# uCCtrl.net
KiCad netlist of a schematic drawn in Altium Designer
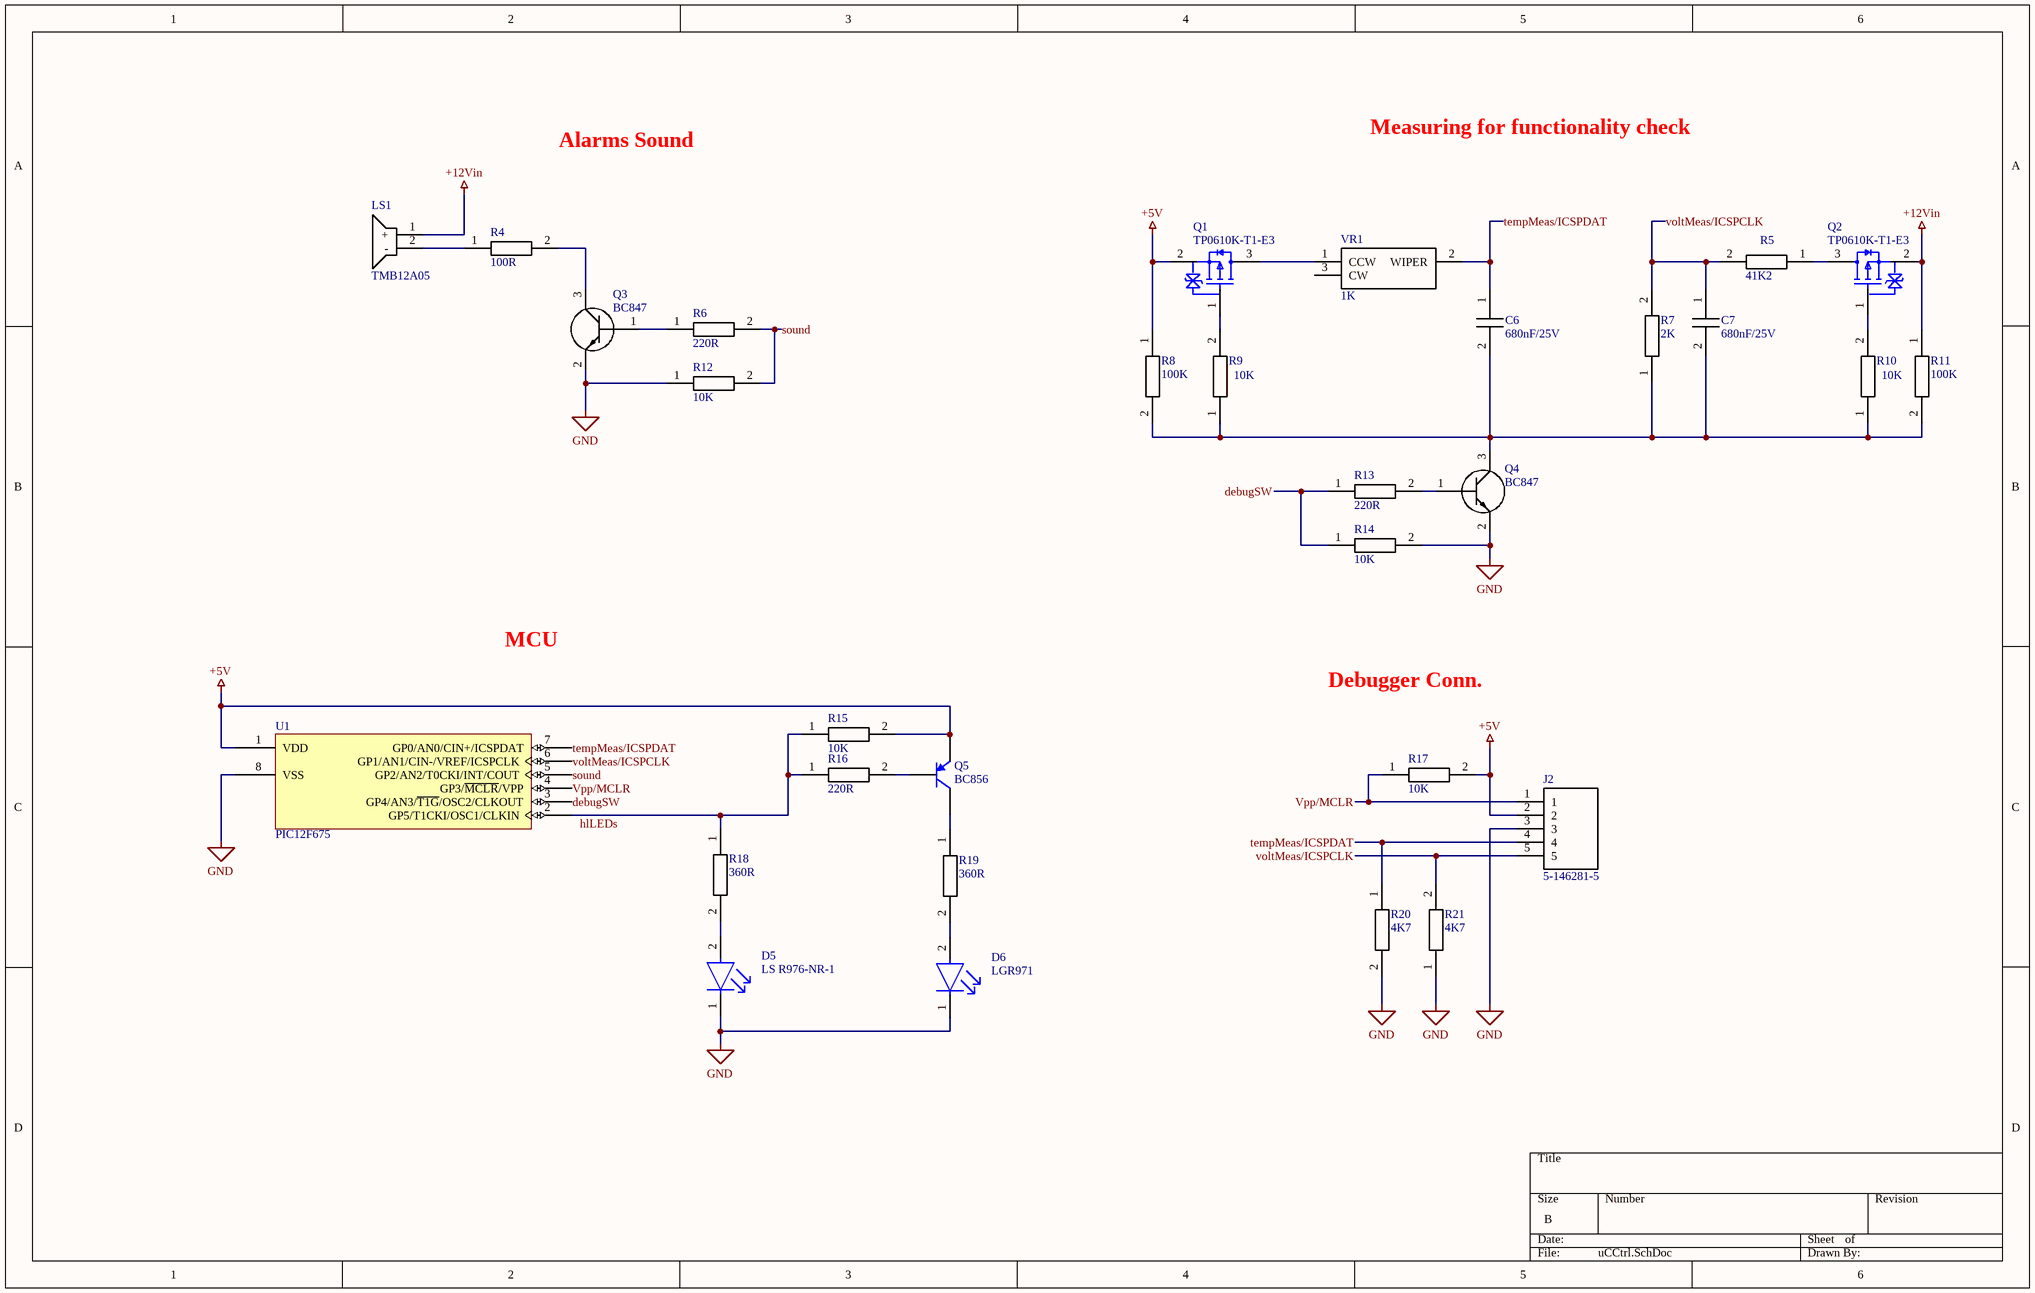
[diagram p0: uCCtrl.SchDoc]

(export (version "E")
  (design (tool "Eeschema 10.0.6"))
  (components
    (comp (ref "C6")
      (value "680nF/25V")
      (footprint "SamacSys:CAPC2012X95N")
      (description "Capacitor")
      (fields (field (name "MANUFACTURER_PART_NUMBER") "GRM219B31E684KA88D"))
      (libsource (lib "*") (part "GRM219B31E684KA88D"))
    )
    (comp (ref "C7")
      (value "680nF/25V")
      (footprint "SamacSys:CAPC2012X95N")
      (description "Capacitor")
      (fields (field (name "MANUFACTURER_PART_NUMBER") "GRM219B31E684KA88D"))
      (libsource (lib "*") (part "GRM219B31E684KA88D"))
    )
    (comp (ref "D5")
      (value "LS R976-NR-1")
      (footprint "FP-LS_R976-MFG")
      (description "LED RED DIFFUSED 0805 SMD")
      (libsource (lib "Altium Content Vault") (part "8706943c75ba83719d021d2fdc84c58"))
    )
    (comp (ref "D6")
      (value "LGR971")
      (footprint "FP-LG_R971-MFG")
      (description "LED GREEN DIFFUSED 0805 SMD")
      (libsource (lib "Altium Content Vault") (part "8706943c75ba83719d021d2fdc84c58"))
    )
    (comp (ref "J2")
      (value "5-146281-5")
      (footprint "SamacSys:HDRV5W67P0X254_1X5_1229X234X821P")
      (description "Connector")
      (fields (field (name "MOUSER PART NUMBER") "571-5-146281-5"))
      (libsource (lib "*") (part "5-146281-5"))
    )
    (comp (ref "LS1")
      (value "TMB12A05")
      (footprint "SamacSys:TMB12A05")
      (description "Loudspeaker or Buzzer")
      (libsource (lib "*") (part "TMB12A05"))
    )
    (comp (ref "Q1")
      (value "TP0610K-T1-E3")
      (footprint "FP-S-03946-MFG")
      (description "MOSFET P-CH 60V 185MA SOT23-3")
      (fields
        (field (name "MANUFACTURER") "Vishay")
        (field (name "OCTOPART") "https://octopart.com/tp0610k-t1-e3-vishay-40944172")
      )
      (libsource (lib "Altium Content Vault") (part "bc9d61678d3f6143cc1ffb3a369bd6c"))
    )
    (comp (ref "Q2")
      (value "TP0610K-T1-E3")
      (footprint "FP-S-03946-MFG")
      (description "MOSFET P-CH 60V 185MA SOT23-3")
      (fields
        (field (name "MANUFACTURER") "Vishay")
        (field (name "OCTOPART") "https://octopart.com/tp0610k-t1-e3-vishay-40944172")
      )
      (libsource (lib "Altium Content Vault") (part "bc9d61678d3f6143cc1ffb3a369bd6c"))
    )
    (comp (ref "Q3")
      (value "BC847")
      (footprint "SamacSys:BC847215")
      (description "Transistor BJT NPN")
      (fields
        (field (name "MANUFACTURER_PART_NUMBER") "BC847,215")
        (field (name "MOUSER PART NUMBER") "771-BC847215")
      )
      (libsource (lib "*") (part "BC847,215"))
    )
    (comp (ref "Q4")
      (value "BC847")
      (footprint "SamacSys:BC847215")
      (description "Transistor BJT NPN")
      (fields
        (field (name "MANUFACTURER_PART_NUMBER") "BC847,215")
        (field (name "MOUSER PART NUMBER") "771-BC847215")
      )
      (libsource (lib "*") (part "BC847,215"))
    )
    (comp (ref "Q5")
      (value "BC856")
      (footprint "NXP-SOT23-3_V")
      (description "PNP General Purpose Transistor, 65 V, -65 to 150 degC, 3-Pin SOT23, RoHS")
      (fields (field (name "MANUFACTURER") "NXP"))
      (libsource (lib "Altium Content Vault") (part "BJT-PNP-BEC-3"))
    )
    (comp (ref "R4")
      (value "100R")
      (footprint "SamacSys:RESC2012X60N")
      (description "Resistor")
      (fields
        (field (name "MANUFACTURER_PART_NUMBER") "CRCW0805100RFKEAHP")
        (field (name "MOUSER PART NUMBER") "71-CRCW0805100RFKEAH")
      )
      (libsource (lib "*") (part "CRCW0805100RFKEAHP"))
    )
    (comp (ref "R5")
      (value "41K2")
      (footprint "SamacSys:RESC2012X65N")
      (description "Resistor")
      (fields (field (name "MANUFACTURER_PART_NUMBER") "CPF0805B41K2E1"))
      (libsource (lib "*") (part "CPF0805B41K2E1"))
    )
    (comp (ref "R6")
      (value "220R")
      (footprint "SamacSys:RESC2012X65N")
      (description "Resistor")
      (fields (field (name "MANUFACTURER_PART_NUMBER") "CPF0805B220RE"))
      (libsource (lib "*") (part "CPF0805B220RE"))
    )
    (comp (ref "R7")
      (value "2K")
      (footprint "SamacSys:RESC2012X65N")
      (description "Resistor")
      (fields
        (field (name "MANUFACTURER_PART_NUMBER") "CPF0805B360RE1")
        (field (name "MOUSER PART NUMBER") "279-CPF0805B360RE1")
      )
      (libsource (lib "*") (part "CPF0805B360RE1"))
    )
    (comp (ref "R8")
      (value "100K")
      (footprint "SamacSys:RESC2012X65N")
      (description "Resistor")
      (fields
        (field (name "MANUFACTURER_PART_NUMBER") "CPF0805B360RE1")
        (field (name "MOUSER PART NUMBER") "279-CPF0805B360RE1")
      )
      (libsource (lib "*") (part "CPF0805B360RE1"))
    )
    (comp (ref "R9")
      (value "10K")
      (footprint "SamacSys:RESC2012X65N")
      (description "Resistor")
      (fields
        (field (name "MANUFACTURER_PART_NUMBER") "CPF0805B360RE1")
        (field (name "MOUSER PART NUMBER") "279-CPF0805B360RE1")
      )
      (libsource (lib "*") (part "CPF0805B360RE1"))
    )
    (comp (ref "R10")
      (value "10K")
      (footprint "SamacSys:RESC2012X65N")
      (description "Resistor")
      (fields
        (field (name "MANUFACTURER_PART_NUMBER") "CPF0805B360RE1")
        (field (name "MOUSER PART NUMBER") "279-CPF0805B360RE1")
      )
      (libsource (lib "*") (part "CPF0805B360RE1"))
    )
    (comp (ref "R11")
      (value "100K")
      (footprint "SamacSys:RESC2012X65N")
      (description "Resistor")
      (fields
        (field (name "MANUFACTURER_PART_NUMBER") "CPF0805B360RE1")
        (field (name "MOUSER PART NUMBER") "279-CPF0805B360RE1")
      )
      (libsource (lib "*") (part "CPF0805B360RE1"))
    )
    (comp (ref "R12")
      (value "10K")
      (footprint "SamacSys:RESC2012X65N")
      (description "Resistor")
      (fields (field (name "MANUFACTURER_PART_NUMBER") "CPF0805B220RE"))
      (libsource (lib "*") (part "CPF0805B220RE"))
    )
    (comp (ref "R13")
      (value "220R")
      (footprint "SamacSys:RESC2012X65N")
      (description "Resistor")
      (fields (field (name "MANUFACTURER_PART_NUMBER") "CPF0805B220RE"))
      (libsource (lib "*") (part "CPF0805B220RE"))
    )
    (comp (ref "R14")
      (value "10K")
      (footprint "SamacSys:RESC2012X65N")
      (description "Resistor")
      (fields (field (name "MANUFACTURER_PART_NUMBER") "CPF0805B220RE"))
      (libsource (lib "*") (part "CPF0805B220RE"))
    )
    (comp (ref "R15")
      (value "10K")
      (footprint "SamacSys:RESC2012X65N")
      (description "Resistor")
      (fields (field (name "MANUFACTURER_PART_NUMBER") "CPF0805B220RE"))
      (libsource (lib "*") (part "CPF0805B220RE"))
    )
    (comp (ref "R16")
      (value "220R")
      (footprint "SamacSys:RESC2012X65N")
      (description "Resistor")
      (fields (field (name "MANUFACTURER_PART_NUMBER") "CPF0805B220RE"))
      (libsource (lib "*") (part "CPF0805B220RE"))
    )
    (comp (ref "R17")
      (value "10K")
      (footprint "SamacSys:RESC2012X65N")
      (description "Resistor")
      (fields
        (field (name "MANUFACTURER_PART_NUMBER") "CPF0805B360RE1")
        (field (name "MOUSER PART NUMBER") "279-CPF0805B360RE1")
      )
      (libsource (lib "*") (part "CPF0805B360RE1"))
    )
    (comp (ref "R18")
      (value "360R")
      (footprint "SamacSys:RESC2012X65N")
      (description "Resistor")
      (fields
        (field (name "MANUFACTURER_PART_NUMBER") "CPF0805B360RE1")
        (field (name "MOUSER PART NUMBER") "279-CPF0805B360RE1")
      )
      (libsource (lib "*") (part "CPF0805B360RE1"))
    )
    (comp (ref "R19")
      (value "360R")
      (footprint "SamacSys:RESC2012X65N")
      (description "Resistor")
      (fields
        (field (name "MANUFACTURER_PART_NUMBER") "CPF0805B360RE1")
        (field (name "MOUSER PART NUMBER") "279-CPF0805B360RE1")
      )
      (libsource (lib "*") (part "CPF0805B360RE1"))
    )
    (comp (ref "R20")
      (value "4K7")
      (footprint "SamacSys:RESC2012X65N")
      (description "Resistor")
      (fields
        (field (name "MANUFACTURER_PART_NUMBER") "CPF0805B360RE1")
        (field (name "MOUSER PART NUMBER") "279-CPF0805B360RE1")
      )
      (libsource (lib "*") (part "CPF0805B360RE1"))
    )
    (comp (ref "R21")
      (value "4K7")
      (footprint "SamacSys:RESC2012X65N")
      (description "Resistor")
      (fields
        (field (name "MANUFACTURER_PART_NUMBER") "CPF0805B360RE1")
        (field (name "MOUSER PART NUMBER") "279-CPF0805B360RE1")
      )
      (libsource (lib "*") (part "CPF0805B360RE1"))
    )
    (comp (ref "U1")
      (value "PIC12F675")
      (footprint "PDIP300-P8")
      (description "FLASH-Based 8-Bit CMOS Microcontroller, 10-Bit A/D, 8-Pin PDIP, Industrial Temperature")
      (libsource (lib "Altium Content Vault") (part "MC-8B-12F675-IL8"))
    )
    (comp (ref "VR1")
      (value "1K")
      (footprint "SamacSys:23SR1KLFTR")
      (description "Variable Resistor")
      (fields (field (name "MANUFACTURER_PART_NUMBER") "23SR1KLFTR"))
      (libsource (lib "*") (part "23SR1KLFTR"))
    )
  )
  (nets
    (net (code "1") (name "+5V") (class "Default")
      (node (ref "J2") (pin "2") (pinfunction "2_2") (pintype "passive"))
      (node (ref "Q1") (pin "2") (pinfunction "S_2") (pintype "passive"))
      (node (ref "Q5") (pin "2") (pinfunction "E_2") (pintype "passive"))
      (node (ref "R15") (pin "2") (pinfunction "2_2") (pintype "passive"))
      (node (ref "R17") (pin "2") (pinfunction "2_2") (pintype "passive"))
      (node (ref "R8") (pin "1") (pinfunction "1_1") (pintype "passive"))
      (node (ref "U1") (pin "1") (pinfunction "VDD_1") (pintype "power_in"))
    )
    (net (code "2") (name "+12Vin") (class "Default")
      (node (ref "LS1") (pin "1") (pinfunction "+_1") (pintype "passive"))
      (node (ref "Q2") (pin "2") (pinfunction "S_2") (pintype "passive"))
      (node (ref "R11") (pin "1") (pinfunction "1_1") (pintype "passive"))
    )
    (net (code "3") (name "/Vpp{slash}MCLR") (class "Default")
      (node (ref "J2") (pin "1") (pinfunction "1_1") (pintype "passive"))
      (node (ref "R17") (pin "1") (pinfunction "1_1") (pintype "passive"))
      (node (ref "U1") (pin "4") (pinfunction "GP3/~{MCLR}/VPP_4") (pintype "bidirectional"))
    )
    (net (code "4") (name "/debugSW") (class "Default")
      (node (ref "R13") (pin "1") (pinfunction "1_1") (pintype "passive"))
      (node (ref "R14") (pin "1") (pinfunction "1_1") (pintype "passive"))
      (node (ref "U1") (pin "3") (pinfunction "GP4/AN3/~{T1G}/OSC2/CLKOUT_3") (pintype "bidirectional"))
    )
    (net (code "5") (name "/hlLEDs") (class "Default")
      (node (ref "R15") (pin "1") (pinfunction "1_1") (pintype "passive"))
      (node (ref "R16") (pin "1") (pinfunction "1_1") (pintype "passive"))
      (node (ref "R18") (pin "1") (pinfunction "1_1") (pintype "passive"))
      (node (ref "U1") (pin "2") (pinfunction "GP5/T1CKI/OSC1/CLKIN_2") (pintype "bidirectional"))
    )
    (net (code "6") (name "/sound") (class "Default")
      (node (ref "R12") (pin "2") (pinfunction "2_2") (pintype "passive"))
      (node (ref "R6") (pin "2") (pinfunction "2_2") (pintype "passive"))
      (node (ref "U1") (pin "5") (pinfunction "GP2/AN2/T0CKI/INT/COUT_5") (pintype "bidirectional"))
    )
    (net (code "7") (name "/tempMeas{slash}ICSPDAT") (class "Default")
      (node (ref "C6") (pin "1") (pinfunction "1_1") (pintype "passive"))
      (node (ref "J2") (pin "4") (pinfunction "4_4") (pintype "passive"))
      (node (ref "R20") (pin "1") (pinfunction "1_1") (pintype "passive"))
      (node (ref "U1") (pin "7") (pinfunction "GP0/AN0/CIN+/ICSPDAT_7") (pintype "bidirectional"))
      (node (ref "VR1") (pin "2") (pinfunction "WIPER_2") (pintype "passive"))
    )
    (net (code "8") (name "/voltMeas{slash}ICSPCLK") (class "Default")
      (node (ref "C7") (pin "1") (pinfunction "1_1") (pintype "passive"))
      (node (ref "J2") (pin "5") (pinfunction "5_5") (pintype "passive"))
      (node (ref "R21") (pin "2") (pinfunction "2_2") (pintype "passive"))
      (node (ref "R5") (pin "2") (pinfunction "2_2") (pintype "passive"))
      (node (ref "R7") (pin "2") (pinfunction "2_2") (pintype "passive"))
      (node (ref "U1") (pin "6") (pinfunction "GP1/AN1/CIN-/VREF/ICSPCLK_6") (pintype "bidirectional"))
    )
    (net (code "9") (name "GND") (class "Default")
      (node (ref "D5") (pin "1") (pinfunction "C_1") (pintype "passive"))
      (node (ref "D6") (pin "1") (pinfunction "C_1") (pintype "passive"))
      (node (ref "J2") (pin "3") (pinfunction "3_3") (pintype "passive"))
      (node (ref "Q3") (pin "2") (pinfunction "E_2") (pintype "passive"))
      (node (ref "Q4") (pin "2") (pinfunction "E_2") (pintype "passive"))
      (node (ref "R12") (pin "1") (pinfunction "1_1") (pintype "passive"))
      (node (ref "R14") (pin "2") (pinfunction "2_2") (pintype "passive"))
      (node (ref "R20") (pin "2") (pinfunction "2_2") (pintype "passive"))
      (node (ref "R21") (pin "1") (pinfunction "1_1") (pintype "passive"))
      (node (ref "U1") (pin "8") (pinfunction "VSS_8") (pintype "power_in"))
    )
    (net (code "10") (name "Net-(D5-A)") (class "Default")
      (node (ref "D5") (pin "2") (pinfunction "A_2") (pintype "passive"))
      (node (ref "R18") (pin "2") (pinfunction "2_2") (pintype "passive"))
    )
    (net (code "11") (name "Net-(D6-A)") (class "Default")
      (node (ref "D6") (pin "2") (pinfunction "A_2") (pintype "passive"))
      (node (ref "R19") (pin "2") (pinfunction "2_2") (pintype "passive"))
    )
    (net (code "12") (name "Net-(LS1--)") (class "Default")
      (node (ref "LS1") (pin "2") (pinfunction "-_2") (pintype "passive"))
      (node (ref "R4") (pin "1") (pinfunction "1_1") (pintype "passive"))
    )
    (net (code "13") (name "Net-(Q1-D)") (class "Default")
      (node (ref "Q1") (pin "3") (pinfunction "D_3") (pintype "passive"))
      (node (ref "VR1") (pin "1") (pinfunction "CCW_1") (pintype "passive"))
    )
    (net (code "14") (name "Net-(Q1-G)") (class "Default")
      (node (ref "Q1") (pin "1") (pinfunction "G_1") (pintype "passive"))
      (node (ref "R9") (pin "2") (pinfunction "2_2") (pintype "passive"))
    )
    (net (code "15") (name "Net-(Q2-D)") (class "Default")
      (node (ref "Q2") (pin "3") (pinfunction "D_3") (pintype "passive"))
      (node (ref "R5") (pin "1") (pinfunction "1_1") (pintype "passive"))
    )
    (net (code "16") (name "Net-(Q2-G)") (class "Default")
      (node (ref "Q2") (pin "1") (pinfunction "G_1") (pintype "passive"))
      (node (ref "R10") (pin "2") (pinfunction "2_2") (pintype "passive"))
    )
    (net (code "17") (name "Net-(Q3-B)") (class "Default")
      (node (ref "Q3") (pin "1") (pinfunction "B_1") (pintype "passive"))
      (node (ref "R6") (pin "1") (pinfunction "1_1") (pintype "passive"))
    )
    (net (code "18") (name "Net-(Q3-C)") (class "Default")
      (node (ref "Q3") (pin "3") (pinfunction "C_3") (pintype "passive"))
      (node (ref "R4") (pin "2") (pinfunction "2_2") (pintype "passive"))
    )
    (net (code "19") (name "Net-(Q4-B)") (class "Default")
      (node (ref "Q4") (pin "1") (pinfunction "B_1") (pintype "passive"))
      (node (ref "R13") (pin "2") (pinfunction "2_2") (pintype "passive"))
    )
    (net (code "20") (name "Net-(Q4-C)") (class "Default")
      (node (ref "C6") (pin "2") (pinfunction "2_2") (pintype "passive"))
      (node (ref "C7") (pin "2") (pinfunction "2_2") (pintype "passive"))
      (node (ref "Q4") (pin "3") (pinfunction "C_3") (pintype "passive"))
      (node (ref "R10") (pin "1") (pinfunction "1_1") (pintype "passive"))
      (node (ref "R11") (pin "2") (pinfunction "2_2") (pintype "passive"))
      (node (ref "R7") (pin "1") (pinfunction "1_1") (pintype "passive"))
      (node (ref "R8") (pin "2") (pinfunction "2_2") (pintype "passive"))
      (node (ref "R9") (pin "1") (pinfunction "1_1") (pintype "passive"))
    )
    (net (code "21") (name "Net-(Q5-B)") (class "Default")
      (node (ref "Q5") (pin "1") (pinfunction "B_1") (pintype "passive"))
      (node (ref "R16") (pin "2") (pinfunction "2_2") (pintype "passive"))
    )
    (net (code "22") (name "Net-(Q5-C)") (class "Default")
      (node (ref "Q5") (pin "3") (pinfunction "C_3") (pintype "passive"))
      (node (ref "R19") (pin "1") (pinfunction "1_1") (pintype "passive"))
    )
    (net (code "23") (name "unconnected-(VR1-CW-Pad3)") (class "Default")
      (node (ref "VR1") (pin "3") (pinfunction "CW_3") (pintype "passive"))
    )
  )
)
